# 07_-_Current-Temp_Sense.net
KiCad netlist of a schematic drawn in Altium Designer
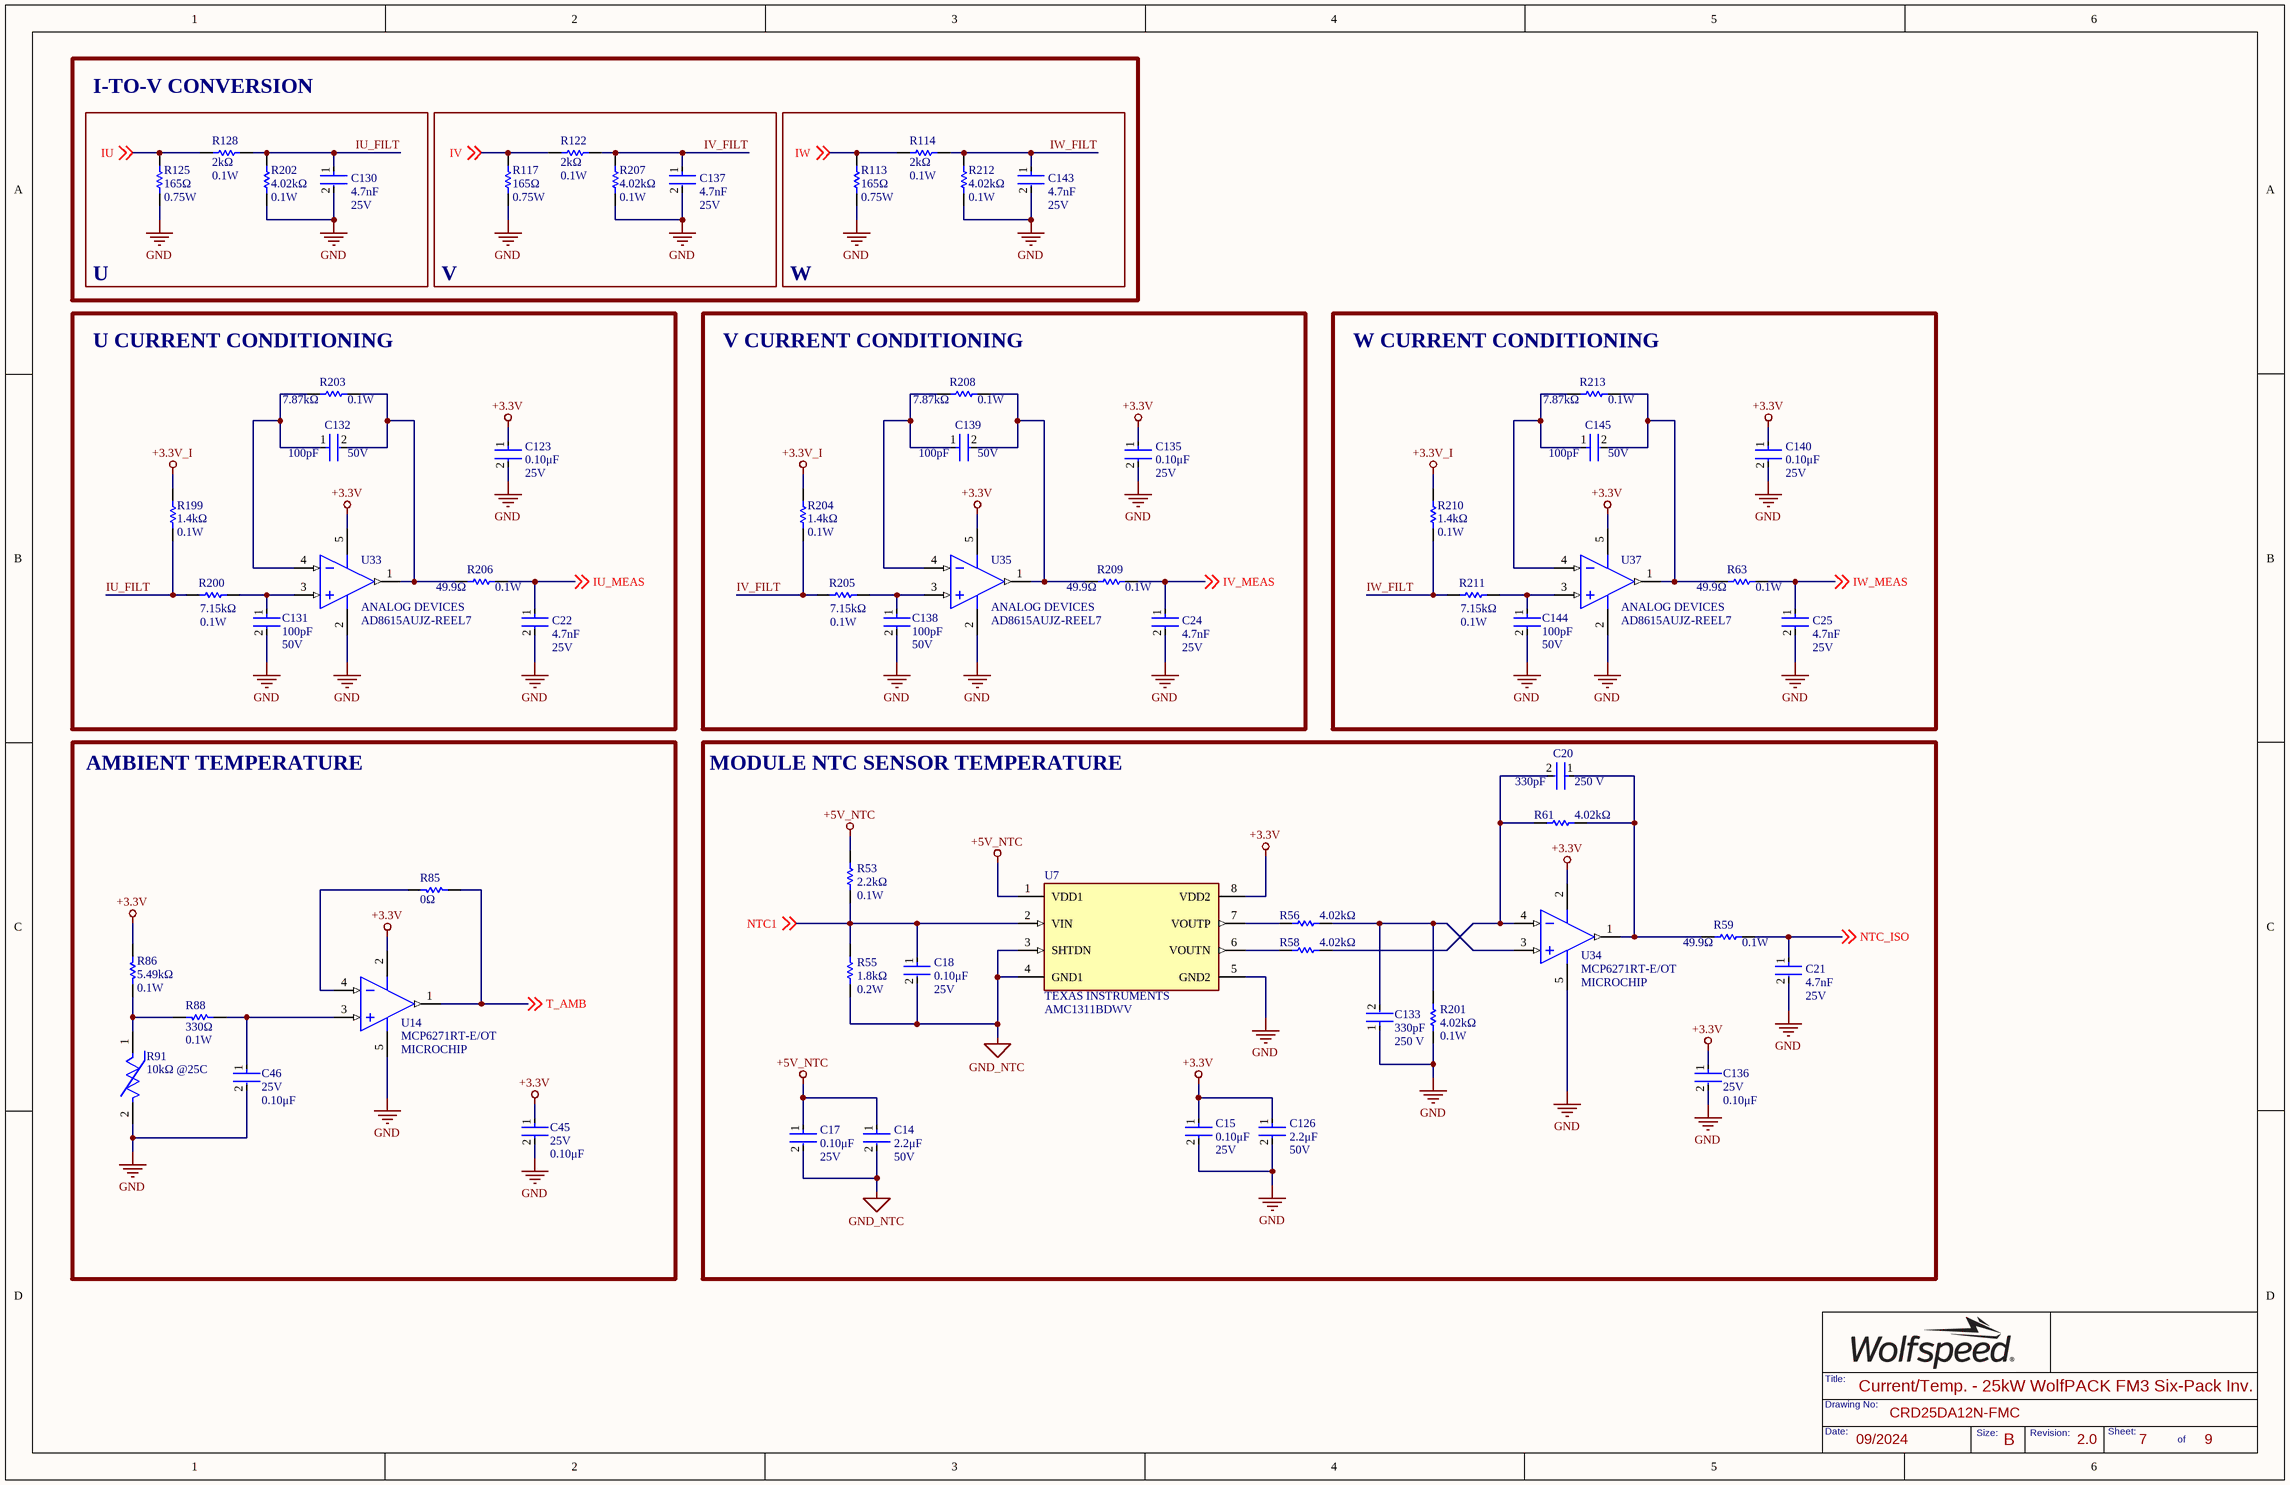
[diagram p0: 07 - Current-Temp Sense.SchDoc]

(export (version "E")
  (design (tool "Eeschema 10.0.6"))
  (components
    (comp (ref "C14")
      (value "GRT188R61H225ME13D")
      (footprint "FP-C0603C-CF-IPC_B")
      (description "CAP CER 2.2UF 50V X5R 0603")
      (fields
        (field (name "MANUFACTURER") "MURATA")
        (field (name "TOLERANCE") "20%")
        (field (name "VOLTAGE RATING") "50V")
        (field (name "CAPACITANCE") "2.2μF")
      )
      (libsource (lib "Inverter_25kW") (part "GRT188R61H225ME13D"))
    )
    (comp (ref "C15")
      (value "C0603C104K3RACTU")
      (footprint "FP-C0603C-CF-IPC_B")
      (description "CAP CER 0.1UF 25V X7R 0603")
      (fields
        (field (name "VOLTAGE RATING") "25V")
        (field (name "OCTOPART") "https://octopart.com/c0603c104k3ractu-kemet-127541")
        (field (name "MANUFACTURER") "KEMET")
        (field (name "CAPACITANCE") "0.10μF")
      )
      (libsource (lib "Altium Content Vault") (part "b4654b650e69147ec39a6b967a45e02"))
    )
    (comp (ref "C17")
      (value "C0603C104K3RACTU")
      (footprint "FP-C0603C-CF-IPC_B")
      (description "CAP CER 0.1UF 25V X7R 0603")
      (fields
        (field (name "VOLTAGE RATING") "25V")
        (field (name "OCTOPART") "https://octopart.com/c0603c104k3ractu-kemet-127541")
        (field (name "MANUFACTURER") "KEMET")
        (field (name "CAPACITANCE") "0.10μF")
      )
      (libsource (lib "Altium Content Vault") (part "b4654b650e69147ec39a6b967a45e02"))
    )
    (comp (ref "C18")
      (value "C0603C104K3RACTU")
      (footprint "FP-C0603C-CF-IPC_B")
      (description "CAP CER 0.1UF 25V X7R 0603")
      (fields
        (field (name "VOLTAGE RATING") "25V")
        (field (name "OCTOPART") "https://octopart.com/c0603c104k3ractu-kemet-127541")
        (field (name "MANUFACTURER") "KEMET")
        (field (name "CAPACITANCE") "0.10μF")
      )
      (libsource (lib "Altium Content Vault") (part "b4654b650e69147ec39a6b967a45e02"))
    )
    (comp (ref "C20")
      (value "330pF")
      (footprint "FP-C0603C-CF-IPC_B")
      (description "CAP CER 330PF 250V C0G/NP0 0603")
      (fields
        (field (name "OCTOPART") "https://octopart.com/c0603c331jagac7867-kemet-83501965")
        (field (name "MANUFACTURER PART NUMBER") "C0603C331JAGAC7867")
        (field (name "VOLTAGE RATING") "250 V")
      )
      (libsource (lib "Altium Content Vault") (part "b4654b650e69147ec39a6b967a45e02"))
    )
    (comp (ref "C21")
      (value "C0603C472K3RAC7867")
      (footprint "FP-C0603C-CF-IPC_B")
      (description "CAP CER 4700PF 25V 10% X7R 0603")
      (fields
        (field (name "MANUFACTURER") "KEMET")
        (field (name "MANUFACTURER PART NUMBER") "C0603C472K3RACTU")
        (field (name "VOLTAGE RATING") "25V")
        (field (name "CAPACITANCE") "4.7nF")
      )
      (libsource (lib "Inverter_25kW") (part "C0603C472K3RAC7867"))
    )
    (comp (ref "C22")
      (value "C0603C472K3RAC7867")
      (footprint "FP-C0603C-CF-IPC_B")
      (description "CAP CER 4700PF 25V 10% X7R 0603")
      (fields
        (field (name "MANUFACTURER") "KEMET")
        (field (name "MANUFACTURER PART NUMBER") "C0603C472K3RACTU")
        (field (name "VOLTAGE RATING") "25V")
        (field (name "CAPACITANCE") "4.7nF")
      )
      (libsource (lib "Inverter_25kW") (part "C0603C472K3RAC7867"))
    )
    (comp (ref "C24")
      (value "C0603C472K3RAC7867")
      (footprint "FP-C0603C-CF-IPC_B")
      (description "CAP CER 4700PF 25V 10% X7R 0603")
      (fields
        (field (name "MANUFACTURER") "KEMET")
        (field (name "MANUFACTURER PART NUMBER") "C0603C472K3RACTU")
        (field (name "VOLTAGE RATING") "25V")
        (field (name "CAPACITANCE") "4.7nF")
      )
      (libsource (lib "Inverter_25kW") (part "C0603C472K3RAC7867"))
    )
    (comp (ref "C25")
      (value "C0603C472K3RAC7867")
      (footprint "FP-C0603C-CF-IPC_B")
      (description "CAP CER 4700PF 25V 10% X7R 0603")
      (fields
        (field (name "MANUFACTURER") "KEMET")
        (field (name "MANUFACTURER PART NUMBER") "C0603C472K3RACTU")
        (field (name "VOLTAGE RATING") "25V")
        (field (name "CAPACITANCE") "4.7nF")
      )
      (libsource (lib "Inverter_25kW") (part "C0603C472K3RAC7867"))
    )
    (comp (ref "C45")
      (value "C0603C104K3RACTU")
      (footprint "FP-C0603C-CF-IPC_B")
      (description "CAP CER 0.1UF 25V X7R 0603")
      (fields
        (field (name "VOLTAGE RATING") "25V")
        (field (name "OCTOPART") "https://octopart.com/c0603c104k3ractu-kemet-127541")
        (field (name "MANUFACTURER") "KEMET")
        (field (name "CAPACITANCE") "0.10μF")
      )
      (libsource (lib "Altium Content Vault") (part "b4654b650e69147ec39a6b967a45e02"))
    )
    (comp (ref "C46")
      (value "C0603C104K3RACTU")
      (footprint "FP-C0603C-CF-IPC_B")
      (description "CAP CER 0.1UF 25V X7R 0603")
      (fields
        (field (name "VOLTAGE RATING") "25V")
        (field (name "OCTOPART") "https://octopart.com/c0603c104k3ractu-kemet-127541")
        (field (name "MANUFACTURER") "KEMET")
        (field (name "CAPACITANCE") "0.10μF")
      )
      (libsource (lib "Altium Content Vault") (part "b4654b650e69147ec39a6b967a45e02"))
    )
    (comp (ref "C123")
      (value "C0603C104K3RACTU")
      (footprint "FP-C0603C-CF-IPC_B")
      (description "CAP CER 0.1UF 25V X7R 0603")
      (fields
        (field (name "VOLTAGE RATING") "25V")
        (field (name "OCTOPART") "https://octopart.com/c0603c104k3ractu-kemet-127541")
        (field (name "MANUFACTURER") "KEMET")
        (field (name "CAPACITANCE") "0.10μF")
      )
      (libsource (lib "Altium Content Vault") (part "b4654b650e69147ec39a6b967a45e02"))
    )
    (comp (ref "C126")
      (value "GRT188R61H225ME13D")
      (footprint "FP-C0603C-CF-IPC_B")
      (description "CAP CER 2.2UF 50V X5R 0603")
      (fields
        (field (name "MANUFACTURER") "MURATA")
        (field (name "TOLERANCE") "20%")
        (field (name "VOLTAGE RATING") "50V")
        (field (name "CAPACITANCE") "2.2μF")
      )
      (libsource (lib "Inverter_25kW") (part "GRT188R61H225ME13D"))
    )
    (comp (ref "C130")
      (value "C0603C472K3RAC7867")
      (footprint "FP-C0603C-CF-IPC_B")
      (description "CAP CER 4700PF 25V 10% X7R 0603")
      (fields
        (field (name "MANUFACTURER") "KEMET")
        (field (name "MANUFACTURER PART NUMBER") "C0603C472K3RACTU")
        (field (name "VOLTAGE RATING") "25V")
        (field (name "CAPACITANCE") "4.7nF")
      )
      (libsource (lib "Inverter_25kW") (part "C0603C472K3RAC7867"))
    )
    (comp (ref "C131")
      (value "CL10C101JB8NNNC")
      (footprint "FP-C0603C-CF-IPC_B")
      (description "CAP CER 100PF 50V C0G/NP0 0603")
      (fields
        (field (name "MANUFACTURER") "SAMSUNG")
        (field (name "TOLERANCE") "5%")
        (field (name "CAPACITANCE") "100pF")
        (field (name "VOLTAGE") "50V")
      )
      (libsource (lib "Inverter_25kW") (part "CL10C101JB8NNNC"))
    )
    (comp (ref "C132")
      (value "CL10C101JB8NNNC")
      (footprint "FP-C0603C-CF-IPC_B")
      (description "CAP CER 100PF 50V C0G/NP0 0603")
      (fields
        (field (name "MANUFACTURER") "SAMSUNG")
        (field (name "TOLERANCE") "5%")
        (field (name "CAPACITANCE") "100pF")
        (field (name "VOLTAGE") "50V")
      )
      (libsource (lib "Inverter_25kW") (part "CL10C101JB8NNNC"))
    )
    (comp (ref "C133")
      (value "330pF")
      (footprint "FP-C0603C-CF-IPC_B")
      (description "CAP CER 330PF 250V C0G/NP0 0603")
      (fields
        (field (name "OCTOPART") "https://octopart.com/c0603c331jagac7867-kemet-83501965")
        (field (name "MANUFACTURER PART NUMBER") "C0603C331JAGAC7867")
        (field (name "VOLTAGE RATING") "250 V")
      )
      (libsource (lib "Altium Content Vault") (part "b4654b650e69147ec39a6b967a45e02"))
    )
    (comp (ref "C135")
      (value "C0603C104K3RACTU")
      (footprint "FP-C0603C-CF-IPC_B")
      (description "CAP CER 0.1UF 25V X7R 0603")
      (fields
        (field (name "VOLTAGE RATING") "25V")
        (field (name "OCTOPART") "https://octopart.com/c0603c104k3ractu-kemet-127541")
        (field (name "MANUFACTURER") "KEMET")
        (field (name "CAPACITANCE") "0.10μF")
      )
      (libsource (lib "Altium Content Vault") (part "b4654b650e69147ec39a6b967a45e02"))
    )
    (comp (ref "C136")
      (value "C0603C104K3RACTU")
      (footprint "FP-C0603C-CF-IPC_B")
      (description "CAP CER 0.1UF 25V X7R 0603")
      (fields
        (field (name "VOLTAGE RATING") "25V")
        (field (name "OCTOPART") "https://octopart.com/c0603c104k3ractu-kemet-127541")
        (field (name "MANUFACTURER") "KEMET")
        (field (name "CAPACITANCE") "0.10μF")
      )
      (libsource (lib "Altium Content Vault") (part "b4654b650e69147ec39a6b967a45e02"))
    )
    (comp (ref "C137")
      (value "C0603C472K3RAC7867")
      (footprint "FP-C0603C-CF-IPC_B")
      (description "CAP CER 4700PF 25V 10% X7R 0603")
      (fields
        (field (name "MANUFACTURER") "KEMET")
        (field (name "MANUFACTURER PART NUMBER") "C0603C472K3RACTU")
        (field (name "VOLTAGE RATING") "25V")
        (field (name "CAPACITANCE") "4.7nF")
      )
      (libsource (lib "Inverter_25kW") (part "C0603C472K3RAC7867"))
    )
    (comp (ref "C138")
      (value "CL10C101JB8NNNC")
      (footprint "FP-C0603C-CF-IPC_B")
      (description "CAP CER 100PF 50V C0G/NP0 0603")
      (fields
        (field (name "MANUFACTURER") "SAMSUNG")
        (field (name "TOLERANCE") "5%")
        (field (name "CAPACITANCE") "100pF")
        (field (name "VOLTAGE") "50V")
      )
      (libsource (lib "Inverter_25kW") (part "CL10C101JB8NNNC"))
    )
    (comp (ref "C139")
      (value "CL10C101JB8NNNC")
      (footprint "FP-C0603C-CF-IPC_B")
      (description "CAP CER 100PF 50V C0G/NP0 0603")
      (fields
        (field (name "MANUFACTURER") "SAMSUNG")
        (field (name "TOLERANCE") "5%")
        (field (name "CAPACITANCE") "100pF")
        (field (name "VOLTAGE") "50V")
      )
      (libsource (lib "Inverter_25kW") (part "CL10C101JB8NNNC"))
    )
    (comp (ref "C140")
      (value "C0603C104K3RACTU")
      (footprint "FP-C0603C-CF-IPC_B")
      (description "CAP CER 0.1UF 25V X7R 0603")
      (fields
        (field (name "VOLTAGE RATING") "25V")
        (field (name "OCTOPART") "https://octopart.com/c0603c104k3ractu-kemet-127541")
        (field (name "MANUFACTURER") "KEMET")
        (field (name "CAPACITANCE") "0.10μF")
      )
      (libsource (lib "Altium Content Vault") (part "b4654b650e69147ec39a6b967a45e02"))
    )
    (comp (ref "C143")
      (value "C0603C472K3RAC7867")
      (footprint "FP-C0603C-CF-IPC_B")
      (description "CAP CER 4700PF 25V 10% X7R 0603")
      (fields
        (field (name "MANUFACTURER") "KEMET")
        (field (name "MANUFACTURER PART NUMBER") "C0603C472K3RACTU")
        (field (name "VOLTAGE RATING") "25V")
        (field (name "CAPACITANCE") "4.7nF")
      )
      (libsource (lib "Inverter_25kW") (part "C0603C472K3RAC7867"))
    )
    (comp (ref "C144")
      (value "CL10C101JB8NNNC")
      (footprint "FP-C0603C-CF-IPC_B")
      (description "CAP CER 100PF 50V C0G/NP0 0603")
      (fields
        (field (name "MANUFACTURER") "SAMSUNG")
        (field (name "TOLERANCE") "5%")
        (field (name "CAPACITANCE") "100pF")
        (field (name "VOLTAGE") "50V")
      )
      (libsource (lib "Inverter_25kW") (part "CL10C101JB8NNNC"))
    )
    (comp (ref "C145")
      (value "CL10C101JB8NNNC")
      (footprint "FP-C0603C-CF-IPC_B")
      (description "CAP CER 100PF 50V C0G/NP0 0603")
      (fields
        (field (name "MANUFACTURER") "SAMSUNG")
        (field (name "TOLERANCE") "5%")
        (field (name "CAPACITANCE") "100pF")
        (field (name "VOLTAGE") "50V")
      )
      (libsource (lib "Inverter_25kW") (part "CL10C101JB8NNNC"))
    )
    (comp (ref "R53")
      (value "2.2kΩ")
      (footprint "FP-MCR03-IPC_B")
      (description "RES 2.2K OHM 1% 1/10W 0603")
      (fields
        (field (name "POWER") "0.1W")
        (field (name "MANUFACTURER") "YAGEO")
        (field (name "MANUFACTURER PART NUMBER") "RC0603FR-072K2L")
      )
      (libsource (lib "CRD25DA12N-FMC") (part "RC0603FR-072K2L"))
    )
    (comp (ref "R55")
      (value "ERJ-PB3B1801V")
      (footprint "FP-MCR03-IPC_B")
      (description "RES SMD 1.8K OHM 0.1% 1/5W 0603")
      (fields
        (field (name "MANUFACTURER") "PANASONIC")
        (field (name "TOLERANCE") "0.1%")
        (field (name "RESISTANCE") "1.8kΩ")
        (field (name "MAX POWER DISSIPATION") "0.2W")
      )
      (libsource (lib "Inverter_25kW") (part "ERJ-PB3B1801V"))
    )
    (comp (ref "R56")
      (value "ERA3AEB4021V")
      (footprint "FP-MCR03-IPC_B")
      (description "RES SMD 4.02KOHM 0.1% 1/10W 0603")
      (fields
        (field (name "MANUFACTURER") "PANASONIC")
        (field (name "MANUFACTURER PART NUMBER") "ERA-3AEB4021V")
        (field (name "RESISTANCE") "4.02kΩ")
      )
      (libsource (lib "Inverter_25kW") (part "ERA3AEB4021V"))
    )
    (comp (ref "R58")
      (value "ERA3AEB4021V")
      (footprint "FP-MCR03-IPC_B")
      (description "RES SMD 4.02KOHM 0.1% 1/10W 0603")
      (fields
        (field (name "MANUFACTURER") "PANASONIC")
        (field (name "MANUFACTURER PART NUMBER") "ERA-3AEB4021V")
        (field (name "RESISTANCE") "4.02kΩ")
      )
      (libsource (lib "Inverter_25kW") (part "ERA3AEB4021V"))
    )
    (comp (ref "R59")
      (value "ERJ-3EKF49R9V")
      (footprint "FP-MCR03-IPC_B")
      (description "RES SMD 49.9 OHM 1% 1/10W 0603")
      (fields
        (field (name "MANUFACTURER") "PANASONIC")
        (field (name "TOLERANCE") "1%")
        (field (name "RESISTANCE") "49.9Ω")
        (field (name "POWER RATING") "0.1W")
      )
      (libsource (lib "Inverter_25kW") (part "ERJ-3EKF49R9V"))
    )
    (comp (ref "R61")
      (value "ERA3AEB4021V")
      (footprint "FP-MCR03-IPC_B")
      (description "RES SMD 4.02KOHM 0.1% 1/10W 0603")
      (fields
        (field (name "MANUFACTURER") "PANASONIC")
        (field (name "MANUFACTURER PART NUMBER") "ERA-3AEB4021V")
        (field (name "RESISTANCE") "4.02kΩ")
      )
      (libsource (lib "Inverter_25kW") (part "ERA3AEB4021V"))
    )
    (comp (ref "R63")
      (value "ERJ-3EKF49R9V")
      (footprint "FP-MCR03-IPC_B")
      (description "RES SMD 49.9 OHM 1% 1/10W 0603")
      (fields
        (field (name "MANUFACTURER") "PANASONIC")
        (field (name "TOLERANCE") "1%")
        (field (name "RESISTANCE") "49.9Ω")
        (field (name "POWER RATING") "0.1W")
      )
      (libsource (lib "Inverter_25kW") (part "ERJ-3EKF49R9V"))
    )
    (comp (ref "R85")
      (value "CRCW06030000Z0EB")
      (footprint "FP-MCR03-IPC_B")
      (description "RES SMD 0 OHM JUMPER 1/10W 0603")
      (fields
        (field (name "MANUFACTURER") "VISHAY DALE")
        (field (name "MANUFACTURER PART NUMBER") "CRCW06030000Z0EBC")
        (field (name "RESISTANCE") "0Ω")
      )
      (libsource (lib "Inverter_25kW") (part "CRCW06030000Z0EB"))
    )
    (comp (ref "R86")
      (value "5.49kΩ")
      (footprint "FP-MCR03-IPC_B")
      (description "RES 5.49K OHM 1% 1/10W 0603")
      (fields
        (field (name "MANUFACTURER") "YAGEO")
        (field (name "MANUFACTURER PART NUMBER") "RC0603FR-075K49L")
        (field (name "POWER RATING") "0.1W")
      )
      (libsource (lib "CRD25DA12N-FMC") (part "RC0603FR-075K49L"))
    )
    (comp (ref "R88")
      (value "RC0603FR-13330RL")
      (footprint "FP-MCR03-IPC_B")
      (description "RES 330 OHM 1% 1/10W 0603")
      (fields
        (field (name "MANUFACTURER") "YAGEO")
        (field (name "TOLERANCE") "1%")
        (field (name "RESISTANCE") "330Ω")
        (field (name "POWER RATING") "0.1W")
      )
      (libsource (lib "Inverter_25kW") (part "RC0603FR-13330RL"))
    )
    (comp (ref "R91")
      (value "10kΩ @25C")
      (footprint "FP-NCU18-0_15-IPC_B")
      (description "THERMISTOR NTC 10KOHM 3380K 0603")
      (fields
        (field (name "MANUFACTURER") "MURATA")
        (field (name "MANUFACTURER PART NUMBER") "NCU18XH103F6SRB")
      )
      (libsource (lib "Altium Content Vault") (part "3b148a6ebabc5fb4d708a66c052d352"))
    )
    (comp (ref "R113")
      (value "165Ω")
      (footprint "FP-CRCW2010-e3-IPC_B")
      (description "RES SMD 165 OHM 1% 3/4W 2010")
      (fields
        (field (name "MANUFACTURER") "VISHAY")
        (field (name "MANUFACTURER PART NUMBER") "CRCW2010165RFKEF")
        (field (name "POWER") "0.75W")
      )
      (libsource (lib "CRD25DA12N-FMC") (part "CRCW2010165RFKEF"))
    )
    (comp (ref "R114")
      (value "RT0603DRE072KL")
      (footprint "FP-MCR03-IPC_B")
      (description "RES SMD 2K OHM 0.5% 1/10W 0603")
      (fields
        (field (name "MANUFACTURER") "YAGEO")
        (field (name "TOLERANCE") "0.5%")
        (field (name "RESISTANCE") "2kΩ")
        (field (name "POWER RATING") "0.1W")
      )
      (libsource (lib "Inverter_25kW") (part "RT0603DRE072KL"))
    )
    (comp (ref "R117")
      (value "165Ω")
      (footprint "FP-CRCW2010-e3-IPC_B")
      (description "RES SMD 165 OHM 1% 3/4W 2010")
      (fields
        (field (name "MANUFACTURER") "VISHAY")
        (field (name "MANUFACTURER PART NUMBER") "CRCW2010165RFKEF")
        (field (name "POWER") "0.75W")
      )
      (libsource (lib "CRD25DA12N-FMC") (part "CRCW2010165RFKEF"))
    )
    (comp (ref "R122")
      (value "RT0603DRE072KL")
      (footprint "FP-MCR03-IPC_B")
      (description "RES SMD 2K OHM 0.5% 1/10W 0603")
      (fields
        (field (name "MANUFACTURER") "YAGEO")
        (field (name "TOLERANCE") "0.5%")
        (field (name "RESISTANCE") "2kΩ")
        (field (name "POWER RATING") "0.1W")
      )
      (libsource (lib "Inverter_25kW") (part "RT0603DRE072KL"))
    )
    (comp (ref "R125")
      (value "165Ω")
      (footprint "FP-CRCW2010-e3-IPC_B")
      (description "RES SMD 165 OHM 1% 3/4W 2010")
      (fields
        (field (name "MANUFACTURER") "VISHAY")
        (field (name "MANUFACTURER PART NUMBER") "CRCW2010165RFKEF")
        (field (name "POWER") "0.75W")
      )
      (libsource (lib "CRD25DA12N-FMC") (part "CRCW2010165RFKEF"))
    )
    (comp (ref "R128")
      (value "RT0603DRE072KL")
      (footprint "FP-MCR03-IPC_B")
      (description "RES SMD 2K OHM 0.5% 1/10W 0603")
      (fields
        (field (name "MANUFACTURER") "YAGEO")
        (field (name "TOLERANCE") "0.5%")
        (field (name "RESISTANCE") "2kΩ")
        (field (name "POWER RATING") "0.1W")
      )
      (libsource (lib "Inverter_25kW") (part "RT0603DRE072KL"))
    )
    (comp (ref "R199")
      (value "1.4kΩ")
      (footprint "FP-MCR03-IPC_B")
      (description "RES SMD 1.4K OHM 0.5% 1/10W 0603")
      (fields
        (field (name "MANUFACTURER") "YAGEO")
        (field (name "MANUFACTURER PART NUMBER") "RT0603DRD071K4L")
        (field (name "POWER") "0.1W")
      )
      (libsource (lib "CRD25DA12N-FMC") (part "RT0603DRD071K4L"))
    )
    (comp (ref "R200")
      (value "RMCF0603FT7K15")
      (footprint "FP-MCR03-IPC_B")
      (description "RES 7.15K OHM 1% 1/10W 0603")
      (fields
        (field (name "MANUFACTURER") "STACKPOLE")
        (field (name "TOLERANCE") "1%")
        (field (name "RESISTANCE") "7.15kΩ")
        (field (name "POWER RATING") "0.1W")
      )
      (libsource (lib "Inverter_25kW") (part "RMCF0603FT7K15"))
    )
    (comp (ref "R201")
      (value "ERA3AEB4021V")
      (footprint "FP-MCR03-IPC_B")
      (description "RES SMD 4.02KOHM 0.1% 1/10W 0603")
      (fields
        (field (name "MANUFACTURER") "PANASONIC")
        (field (name "MANUFACTURER PART NUMBER") "ERA-3AEB4021V")
        (field (name "POWER") "0.1W")
        (field (name "RESISTANCE") "4.02kΩ")
      )
      (libsource (lib "Inverter_25kW") (part "ERA3AEB4021V"))
    )
    (comp (ref "R202")
      (value "ERA3AEB4021V")
      (footprint "FP-MCR03-IPC_B")
      (description "RES SMD 4.02KOHM 0.1% 1/10W 0603")
      (fields
        (field (name "MANUFACTURER") "PANASONIC")
        (field (name "MANUFACTURER PART NUMBER") "ERA-3AEB4021V")
        (field (name "RESISTANCE") "4.02kΩ")
        (field (name "POWER RATING") "0.1W")
      )
      (libsource (lib "Inverter_25kW") (part "ERA3AEB4021V"))
    )
    (comp (ref "R203")
      (value "RC0603FR-077K87L")
      (footprint "FP-MCR03-IPC_B")
      (description "RES 7.87K OHM 1% 1/10W 0603")
      (fields
        (field (name "MANUFACTURER") "YAGEO")
        (field (name "TOLERANCE") "1%")
        (field (name "RESISTANCE") "7.87kΩ")
        (field (name "MAX POWER DISSIPATION") "0.1W")
      )
      (libsource (lib "Inverter_25kW") (part "RC0603FR-077K87L"))
    )
    (comp (ref "R204")
      (value "1.4kΩ")
      (footprint "FP-MCR03-IPC_B")
      (description "RES SMD 1.4K OHM 0.5% 1/10W 0603")
      (fields
        (field (name "MANUFACTURER") "YAGEO")
        (field (name "MANUFACTURER PART NUMBER") "RT0603DRD071K4L")
        (field (name "POWER") "0.1W")
      )
      (libsource (lib "CRD25DA12N-FMC") (part "RT0603DRD071K4L"))
    )
    (comp (ref "R205")
      (value "RMCF0603FT7K15")
      (footprint "FP-MCR03-IPC_B")
      (description "RES 7.15K OHM 1% 1/10W 0603")
      (fields
        (field (name "MANUFACTURER") "STACKPOLE")
        (field (name "TOLERANCE") "1%")
        (field (name "RESISTANCE") "7.15kΩ")
        (field (name "POWER RATING") "0.1W")
      )
      (libsource (lib "Inverter_25kW") (part "RMCF0603FT7K15"))
    )
    (comp (ref "R206")
      (value "ERJ-3EKF49R9V")
      (footprint "FP-MCR03-IPC_B")
      (description "RES SMD 49.9 OHM 1% 1/10W 0603")
      (fields
        (field (name "MANUFACTURER") "PANASONIC")
        (field (name "TOLERANCE") "1%")
        (field (name "RESISTANCE") "49.9Ω")
        (field (name "POWER RATING") "0.1W")
      )
      (libsource (lib "Inverter_25kW") (part "ERJ-3EKF49R9V"))
    )
    (comp (ref "R207")
      (value "ERA3AEB4021V")
      (footprint "FP-MCR03-IPC_B")
      (description "RES SMD 4.02KOHM 0.1% 1/10W 0603")
      (fields
        (field (name "MANUFACTURER") "PANASONIC")
        (field (name "MANUFACTURER PART NUMBER") "ERA-3AEB4021V")
        (field (name "RESISTANCE") "4.02kΩ")
        (field (name "POWER RATING") "0.1W")
      )
      (libsource (lib "Inverter_25kW") (part "ERA3AEB4021V"))
    )
    (comp (ref "R208")
      (value "RC0603FR-077K87L")
      (footprint "FP-MCR03-IPC_B")
      (description "RES 7.87K OHM 1% 1/10W 0603")
      (fields
        (field (name "MANUFACTURER") "YAGEO")
        (field (name "TOLERANCE") "1%")
        (field (name "RESISTANCE") "7.87kΩ")
        (field (name "MAX POWER DISSIPATION") "0.1W")
      )
      (libsource (lib "Inverter_25kW") (part "RC0603FR-077K87L"))
    )
    (comp (ref "R209")
      (value "ERJ-3EKF49R9V")
      (footprint "FP-MCR03-IPC_B")
      (description "RES SMD 49.9 OHM 1% 1/10W 0603")
      (fields
        (field (name "MANUFACTURER") "PANASONIC")
        (field (name "TOLERANCE") "1%")
        (field (name "RESISTANCE") "49.9Ω")
        (field (name "POWER RATING") "0.1W")
      )
      (libsource (lib "Inverter_25kW") (part "ERJ-3EKF49R9V"))
    )
    (comp (ref "R210")
      (value "1.4kΩ")
      (footprint "FP-MCR03-IPC_B")
      (description "RES SMD 1.4K OHM 0.5% 1/10W 0603")
      (fields
        (field (name "MANUFACTURER") "YAGEO")
        (field (name "MANUFACTURER PART NUMBER") "RT0603DRD071K4L")
        (field (name "POWER") "0.1W")
      )
      (libsource (lib "CRD25DA12N-FMC") (part "RT0603DRD071K4L"))
    )
    (comp (ref "R211")
      (value "RMCF0603FT7K15")
      (footprint "FP-MCR03-IPC_B")
      (description "RES 7.15K OHM 1% 1/10W 0603")
      (fields
        (field (name "MANUFACTURER") "STACKPOLE")
        (field (name "TOLERANCE") "1%")
        (field (name "RESISTANCE") "7.15kΩ")
        (field (name "POWER RATING") "0.1W")
      )
      (libsource (lib "Inverter_25kW") (part "RMCF0603FT7K15"))
    )
    (comp (ref "R212")
      (value "ERA3AEB4021V")
      (footprint "FP-MCR03-IPC_B")
      (description "RES SMD 4.02KOHM 0.1% 1/10W 0603")
      (fields
        (field (name "MANUFACTURER") "PANASONIC")
        (field (name "MANUFACTURER PART NUMBER") "ERA-3AEB4021V")
        (field (name "RESISTANCE") "4.02kΩ")
        (field (name "POWER RATING") "0.1W")
      )
      (libsource (lib "Inverter_25kW") (part "ERA3AEB4021V"))
    )
    (comp (ref "R213")
      (value "RC0603FR-077K87L")
      (footprint "FP-MCR03-IPC_B")
      (description "RES 7.87K OHM 1% 1/10W 0603")
      (fields
        (field (name "MANUFACTURER") "YAGEO")
        (field (name "TOLERANCE") "1%")
        (field (name "RESISTANCE") "7.87kΩ")
        (field (name "MAX POWER DISSIPATION") "0.1W")
      )
      (libsource (lib "Inverter_25kW") (part "RC0603FR-077K87L"))
    )
    (comp (ref "U7")
      (value "AMC1311BDWV")
      (footprint "FP-DWV0008A-MFG")
      (description "IC ISOLATION 8SOIC")
      (fields
        (field (name "MANUFACTURER") "TEXAS INSTRUMENTS")
        (field (name "OCTOPART") "https://octopart.com/amc1311bdwv-texas+instruments-88030782")
      )
      (libsource (lib "Altium Content Vault") (part "59c49c505aa37719ef898ce9673978d"))
    )
    (comp (ref "U14")
      (value "MCP6271RT-E/OT")
      (footprint "ADI-UJ-5_M")
      (description "IC OPAMP GP 1 CIRCUIT SOT23-5")
      (fields
        (field (name "MANUFACTURER PART NUMBER") "MCP6271RT-E/OT")
        (field (name "MANUFACTURER") "MICROCHIP")
      )
      (libsource (lib "CRD25DA12N-FMC") (part "MCP6271RT-E/OT"))
    )
    (comp (ref "U33")
      (value "AD8615AUJZ-REEL7")
      (footprint "ADI-UJ-5_M")
      (description "IC OPAMP GP 1 CIRCUIT TSOT23-5")
      (fields
        (field (name "MANUFACTURER") "ANALOG DEVICES")
        (field (name "GENERIC PART NUMBER") "AD8615")
        (field (name "MANUFACTURER PART NUMBER") "AD8615AUJZ-REEL7")
      )
      (libsource (lib "Altium Content Vault") (part "ADI-ADxxxx-X-5"))
    )
    (comp (ref "U34")
      (value "MCP6271RT-E/OT")
      (footprint "ADI-UJ-5_M")
      (description "IC OPAMP GP 1 CIRCUIT SOT23-5")
      (fields
        (field (name "MANUFACTURER PART NUMBER") "MCP6271RT-E/OT")
        (field (name "MANUFACTURER") "MICROCHIP")
      )
      (libsource (lib "CRD25DA12N-FMC") (part "MCP6271RT-E/OT"))
    )
    (comp (ref "U35")
      (value "AD8615AUJZ-REEL7")
      (footprint "ADI-UJ-5_M")
      (description "IC OPAMP GP 1 CIRCUIT TSOT23-5")
      (fields
        (field (name "MANUFACTURER") "ANALOG DEVICES")
        (field (name "GENERIC PART NUMBER") "AD8615")
        (field (name "MANUFACTURER PART NUMBER") "AD8615AUJZ-REEL7")
      )
      (libsource (lib "Altium Content Vault") (part "ADI-ADxxxx-X-5"))
    )
    (comp (ref "U37")
      (value "AD8615AUJZ-REEL7")
      (footprint "ADI-UJ-5_M")
      (description "IC OPAMP GP 1 CIRCUIT TSOT23-5")
      (fields
        (field (name "MANUFACTURER") "ANALOG DEVICES")
        (field (name "GENERIC PART NUMBER") "AD8615")
        (field (name "MANUFACTURER PART NUMBER") "AD8615AUJZ-REEL7")
      )
      (libsource (lib "Altium Content Vault") (part "ADI-ADxxxx-X-5"))
    )
  )
  (nets
    (net (code "1") (name "+3.3V") (class "Default")
      (node (ref "C123") (pin "1") (pinfunction "1_1") (pintype "passive"))
      (node (ref "C126") (pin "1") (pinfunction "1_1") (pintype "passive"))
      (node (ref "C135") (pin "1") (pinfunction "1_1") (pintype "passive"))
      (node (ref "C136") (pin "1") (pinfunction "1_1") (pintype "passive"))
      (node (ref "C140") (pin "1") (pinfunction "1_1") (pintype "passive"))
      (node (ref "C15") (pin "1") (pinfunction "1_1") (pintype "passive"))
      (node (ref "C45") (pin "1") (pinfunction "1_1") (pintype "passive"))
      (node (ref "R86") (pin "2") (pinfunction "2_2") (pintype "passive"))
      (node (ref "U14") (pin "2") (pinfunction "+V_2") (pintype "power_in"))
      (node (ref "U33") (pin "5") (pinfunction "+V_5") (pintype "power_in"))
      (node (ref "U34") (pin "2") (pinfunction "+V_2") (pintype "power_in"))
      (node (ref "U35") (pin "5") (pinfunction "+V_5") (pintype "power_in"))
      (node (ref "U37") (pin "5") (pinfunction "+V_5") (pintype "power_in"))
      (node (ref "U7") (pin "8") (pinfunction "VDD2_8") (pintype "power_in"))
    )
    (net (code "2") (name "+3.3V_I") (class "Default")
      (node (ref "R199") (pin "2") (pinfunction "2_2") (pintype "passive"))
      (node (ref "R204") (pin "2") (pinfunction "2_2") (pintype "passive"))
      (node (ref "R210") (pin "2") (pinfunction "2_2") (pintype "passive"))
    )
    (net (code "3") (name "+5V_NTC") (class "Default")
      (node (ref "C14") (pin "1") (pinfunction "1_1") (pintype "passive"))
      (node (ref "C17") (pin "1") (pinfunction "1_1") (pintype "passive"))
      (node (ref "R53") (pin "2") (pinfunction "2_2") (pintype "passive"))
      (node (ref "U7") (pin "1") (pinfunction "VDD1_1") (pintype "power_in"))
    )
    (net (code "4") (name "/IU_FILT") (class "Default")
      (node (ref "C130") (pin "1") (pinfunction "1_1") (pintype "passive"))
      (node (ref "R128") (pin "2") (pinfunction "2_2") (pintype "passive"))
      (node (ref "R199") (pin "1") (pinfunction "1_1") (pintype "passive"))
      (node (ref "R200") (pin "1") (pinfunction "1_1") (pintype "passive"))
      (node (ref "R202") (pin "2") (pinfunction "2_2") (pintype "passive"))
    )
    (net (code "5") (name "/IV_FILT") (class "Default")
      (node (ref "C137") (pin "1") (pinfunction "1_1") (pintype "passive"))
      (node (ref "R122") (pin "2") (pinfunction "2_2") (pintype "passive"))
      (node (ref "R204") (pin "1") (pinfunction "1_1") (pintype "passive"))
      (node (ref "R205") (pin "1") (pinfunction "1_1") (pintype "passive"))
      (node (ref "R207") (pin "2") (pinfunction "2_2") (pintype "passive"))
    )
    (net (code "6") (name "/IW_FILT") (class "Default")
      (node (ref "C143") (pin "1") (pinfunction "1_1") (pintype "passive"))
      (node (ref "R114") (pin "2") (pinfunction "2_2") (pintype "passive"))
      (node (ref "R210") (pin "1") (pinfunction "1_1") (pintype "passive"))
      (node (ref "R211") (pin "1") (pinfunction "1_1") (pintype "passive"))
      (node (ref "R212") (pin "2") (pinfunction "2_2") (pintype "passive"))
    )
    (net (code "7") (name "GND") (class "Default")
      (node (ref "C123") (pin "2") (pinfunction "2_2") (pintype "passive"))
      (node (ref "C126") (pin "2") (pinfunction "2_2") (pintype "passive"))
      (node (ref "C130") (pin "2") (pinfunction "2_2") (pintype "passive"))
      (node (ref "C131") (pin "2") (pinfunction "2_2") (pintype "passive"))
      (node (ref "C133") (pin "1") (pinfunction "1_1") (pintype "passive"))
      (node (ref "C135") (pin "2") (pinfunction "2_2") (pintype "passive"))
      (node (ref "C136") (pin "2") (pinfunction "2_2") (pintype "passive"))
      (node (ref "C137") (pin "2") (pinfunction "2_2") (pintype "passive"))
      (node (ref "C138") (pin "2") (pinfunction "2_2") (pintype "passive"))
      (node (ref "C140") (pin "2") (pinfunction "2_2") (pintype "passive"))
      (node (ref "C143") (pin "2") (pinfunction "2_2") (pintype "passive"))
      (node (ref "C144") (pin "2") (pinfunction "2_2") (pintype "passive"))
      (node (ref "C15") (pin "2") (pinfunction "2_2") (pintype "passive"))
      (node (ref "C21") (pin "2") (pinfunction "2_2") (pintype "passive"))
      (node (ref "C22") (pin "2") (pinfunction "2_2") (pintype "passive"))
      (node (ref "C24") (pin "2") (pinfunction "2_2") (pintype "passive"))
      (node (ref "C25") (pin "2") (pinfunction "2_2") (pintype "passive"))
      (node (ref "C45") (pin "2") (pinfunction "2_2") (pintype "passive"))
      (node (ref "C46") (pin "2") (pinfunction "2_2") (pintype "passive"))
      (node (ref "R113") (pin "1") (pinfunction "1_1") (pintype "passive"))
      (node (ref "R117") (pin "1") (pinfunction "1_1") (pintype "passive"))
      (node (ref "R125") (pin "1") (pinfunction "1_1") (pintype "passive"))
      (node (ref "R201") (pin "2") (pinfunction "2_2") (pintype "passive"))
      (node (ref "R202") (pin "1") (pinfunction "1_1") (pintype "passive"))
      (node (ref "R207") (pin "1") (pinfunction "1_1") (pintype "passive"))
      (node (ref "R212") (pin "1") (pinfunction "1_1") (pintype "passive"))
      (node (ref "R91") (pin "2") (pinfunction "2_2") (pintype "passive"))
      (node (ref "U14") (pin "5") (pinfunction "-V_5") (pintype "power_in"))
      (node (ref "U33") (pin "2") (pinfunction "-V_2") (pintype "power_in"))
      (node (ref "U34") (pin "5") (pinfunction "-V_5") (pintype "power_in"))
      (node (ref "U35") (pin "2") (pinfunction "-V_2") (pintype "power_in"))
      (node (ref "U37") (pin "2") (pinfunction "-V_2") (pintype "power_in"))
      (node (ref "U7") (pin "5") (pinfunction "GND2_5") (pintype "power_in"))
    )
    (net (code "8") (name "GND_NTC") (class "Default")
      (node (ref "C14") (pin "2") (pinfunction "2_2") (pintype "passive"))
      (node (ref "C17") (pin "2") (pinfunction "2_2") (pintype "passive"))
      (node (ref "C18") (pin "2") (pinfunction "2_2") (pintype "passive"))
      (node (ref "R55") (pin "1") (pinfunction "1_1") (pintype "passive"))
      (node (ref "U7") (pin "3") (pinfunction "SHTDN_3") (pintype "input"))
      (node (ref "U7") (pin "4") (pinfunction "GND1_4") (pintype "power_in"))
    )
    (net (code "9") (name "IU") (class "Default")
      (node (ref "R125") (pin "2") (pinfunction "2_2") (pintype "passive"))
      (node (ref "R128") (pin "1") (pinfunction "1_1") (pintype "passive"))
    )
    (net (code "10") (name "IU_MEAS") (class "Default")
      (node (ref "C22") (pin "1") (pinfunction "1_1") (pintype "passive"))
      (node (ref "R206") (pin "2") (pinfunction "2_2") (pintype "passive"))
    )
    (net (code "11") (name "IV") (class "Default")
      (node (ref "R117") (pin "2") (pinfunction "2_2") (pintype "passive"))
      (node (ref "R122") (pin "1") (pinfunction "1_1") (pintype "passive"))
    )
    (net (code "12") (name "IV_MEAS") (class "Default")
      (node (ref "C24") (pin "1") (pinfunction "1_1") (pintype "passive"))
      (node (ref "R209") (pin "2") (pinfunction "2_2") (pintype "passive"))
    )
    (net (code "13") (name "IW") (class "Default")
      (node (ref "R113") (pin "2") (pinfunction "2_2") (pintype "passive"))
      (node (ref "R114") (pin "1") (pinfunction "1_1") (pintype "passive"))
    )
    (net (code "14") (name "IW_MEAS") (class "Default")
      (node (ref "C25") (pin "1") (pinfunction "1_1") (pintype "passive"))
      (node (ref "R63") (pin "2") (pinfunction "2_2") (pintype "passive"))
    )
    (net (code "15") (name "NTC1") (class "Default")
      (node (ref "C18") (pin "1") (pinfunction "1_1") (pintype "passive"))
      (node (ref "R53") (pin "1") (pinfunction "1_1") (pintype "passive"))
      (node (ref "R55") (pin "2") (pinfunction "2_2") (pintype "passive"))
      (node (ref "U7") (pin "2") (pinfunction "VIN_2") (pintype "input"))
    )
    (net (code "16") (name "NTC_ISO") (class "Default")
      (node (ref "C21") (pin "1") (pinfunction "1_1") (pintype "passive"))
      (node (ref "R59") (pin "2") (pinfunction "2_2") (pintype "passive"))
    )
    (net (code "17") (name "Net-(R86-Pad1)") (class "Default")
      (node (ref "R86") (pin "1") (pinfunction "1_1") (pintype "passive"))
      (node (ref "R88") (pin "1") (pinfunction "1_1") (pintype "passive"))
      (node (ref "R91") (pin "1") (pinfunction "1_1") (pintype "passive"))
    )
    (net (code "18") (name "Net-(U7-VOUTN)") (class "Default")
      (node (ref "R58") (pin "2") (pinfunction "2_2") (pintype "passive"))
      (node (ref "U7") (pin "6") (pinfunction "VOUTN_6") (pintype "output"))
    )
    (net (code "19") (name "Net-(U7-VOUTP)") (class "Default")
      (node (ref "R56") (pin "2") (pinfunction "2_2") (pintype "passive"))
      (node (ref "U7") (pin "7") (pinfunction "VOUTP_7") (pintype "output"))
    )
    (net (code "20") (name "Net-(U14-+IN)") (class "Default")
      (node (ref "C46") (pin "1") (pinfunction "1_1") (pintype "passive"))
      (node (ref "R88") (pin "2") (pinfunction "2_2") (pintype "passive"))
      (node (ref "U14") (pin "3") (pinfunction "+IN_3") (pintype "input"))
    )
    (net (code "21") (name "Net-(U14--IN)") (class "Default")
      (node (ref "R85") (pin "2") (pinfunction "2_2") (pintype "passive"))
      (node (ref "U14") (pin "4") (pinfunction "-IN_4") (pintype "input"))
    )
    (net (code "22") (name "Net-(U33-+IN)") (class "Default")
      (node (ref "C131") (pin "1") (pinfunction "1_1") (pintype "passive"))
      (node (ref "R200") (pin "2") (pinfunction "2_2") (pintype "passive"))
      (node (ref "U33") (pin "3") (pinfunction "+IN_3") (pintype "input"))
    )
    (net (code "23") (name "Net-(U33--IN)") (class "Default")
      (node (ref "C132") (pin "1") (pinfunction "1_1") (pintype "passive"))
      (node (ref "R203") (pin "1") (pinfunction "1_1") (pintype "passive"))
      (node (ref "U33") (pin "4") (pinfunction "-IN_4") (pintype "input"))
    )
    (net (code "24") (name "Net-(U33-OUT)") (class "Default")
      (node (ref "C132") (pin "2") (pinfunction "2_2") (pintype "passive"))
      (node (ref "R203") (pin "2") (pinfunction "2_2") (pintype "passive"))
      (node (ref "R206") (pin "1") (pinfunction "1_1") (pintype "passive"))
      (node (ref "U33") (pin "1") (pinfunction "OUT_1") (pintype "output"))
    )
    (net (code "25") (name "Net-(U34-+IN)") (class "Default")
      (node (ref "C133") (pin "2") (pinfunction "2_2") (pintype "passive"))
      (node (ref "R201") (pin "1") (pinfunction "1_1") (pintype "passive"))
      (node (ref "R56") (pin "1") (pinfunction "1_1") (pintype "passive"))
      (node (ref "U34") (pin "3") (pinfunction "+IN_3") (pintype "input"))
    )
    (net (code "26") (name "Net-(U34--IN)") (class "Default")
      (node (ref "C20") (pin "2") (pinfunction "2_2") (pintype "passive"))
      (node (ref "R58") (pin "1") (pinfunction "1_1") (pintype "passive"))
      (node (ref "R61") (pin "2") (pinfunction "2_2") (pintype "passive"))
      (node (ref "U34") (pin "4") (pinfunction "-IN_4") (pintype "input"))
    )
    (net (code "27") (name "Net-(U34-OUT)") (class "Default")
      (node (ref "C20") (pin "1") (pinfunction "1_1") (pintype "passive"))
      (node (ref "R59") (pin "1") (pinfunction "1_1") (pintype "passive"))
      (node (ref "R61") (pin "1") (pinfunction "1_1") (pintype "passive"))
      (node (ref "U34") (pin "1") (pinfunction "OUT_1") (pintype "output"))
    )
    (net (code "28") (name "Net-(U35-+IN)") (class "Default")
      (node (ref "C138") (pin "1") (pinfunction "1_1") (pintype "passive"))
      (node (ref "R205") (pin "2") (pinfunction "2_2") (pintype "passive"))
      (node (ref "U35") (pin "3") (pinfunction "+IN_3") (pintype "input"))
    )
    (net (code "29") (name "Net-(U35--IN)") (class "Default")
      (node (ref "C139") (pin "1") (pinfunction "1_1") (pintype "passive"))
      (node (ref "R208") (pin "1") (pinfunction "1_1") (pintype "passive"))
      (node (ref "U35") (pin "4") (pinfunction "-IN_4") (pintype "input"))
    )
    (net (code "30") (name "Net-(U35-OUT)") (class "Default")
      (node (ref "C139") (pin "2") (pinfunction "2_2") (pintype "passive"))
      (node (ref "R208") (pin "2") (pinfunction "2_2") (pintype "passive"))
      (node (ref "R209") (pin "1") (pinfunction "1_1") (pintype "passive"))
      (node (ref "U35") (pin "1") (pinfunction "OUT_1") (pintype "output"))
    )
    (net (code "31") (name "Net-(U37-+IN)") (class "Default")
      (node (ref "C144") (pin "1") (pinfunction "1_1") (pintype "passive"))
      (node (ref "R211") (pin "2") (pinfunction "2_2") (pintype "passive"))
      (node (ref "U37") (pin "3") (pinfunction "+IN_3") (pintype "input"))
    )
    (net (code "32") (name "Net-(U37--IN)") (class "Default")
      (node (ref "C145") (pin "1") (pinfunction "1_1") (pintype "passive"))
      (node (ref "R213") (pin "1") (pinfunction "1_1") (pintype "passive"))
      (node (ref "U37") (pin "4") (pinfunction "-IN_4") (pintype "input"))
    )
    (net (code "33") (name "Net-(U37-OUT)") (class "Default")
      (node (ref "C145") (pin "2") (pinfunction "2_2") (pintype "passive"))
      (node (ref "R213") (pin "2") (pinfunction "2_2") (pintype "passive"))
      (node (ref "R63") (pin "1") (pinfunction "1_1") (pintype "passive"))
      (node (ref "U37") (pin "1") (pinfunction "OUT_1") (pintype "output"))
    )
    (net (code "34") (name "T_AMB") (class "Default")
      (node (ref "R85") (pin "1") (pinfunction "1_1") (pintype "passive"))
      (node (ref "U14") (pin "1") (pinfunction "OUT_1") (pintype "output"))
    )
  )
)
